# CH32X035F7.net
KiCad netlist of a schematic drawn in Altium Designer
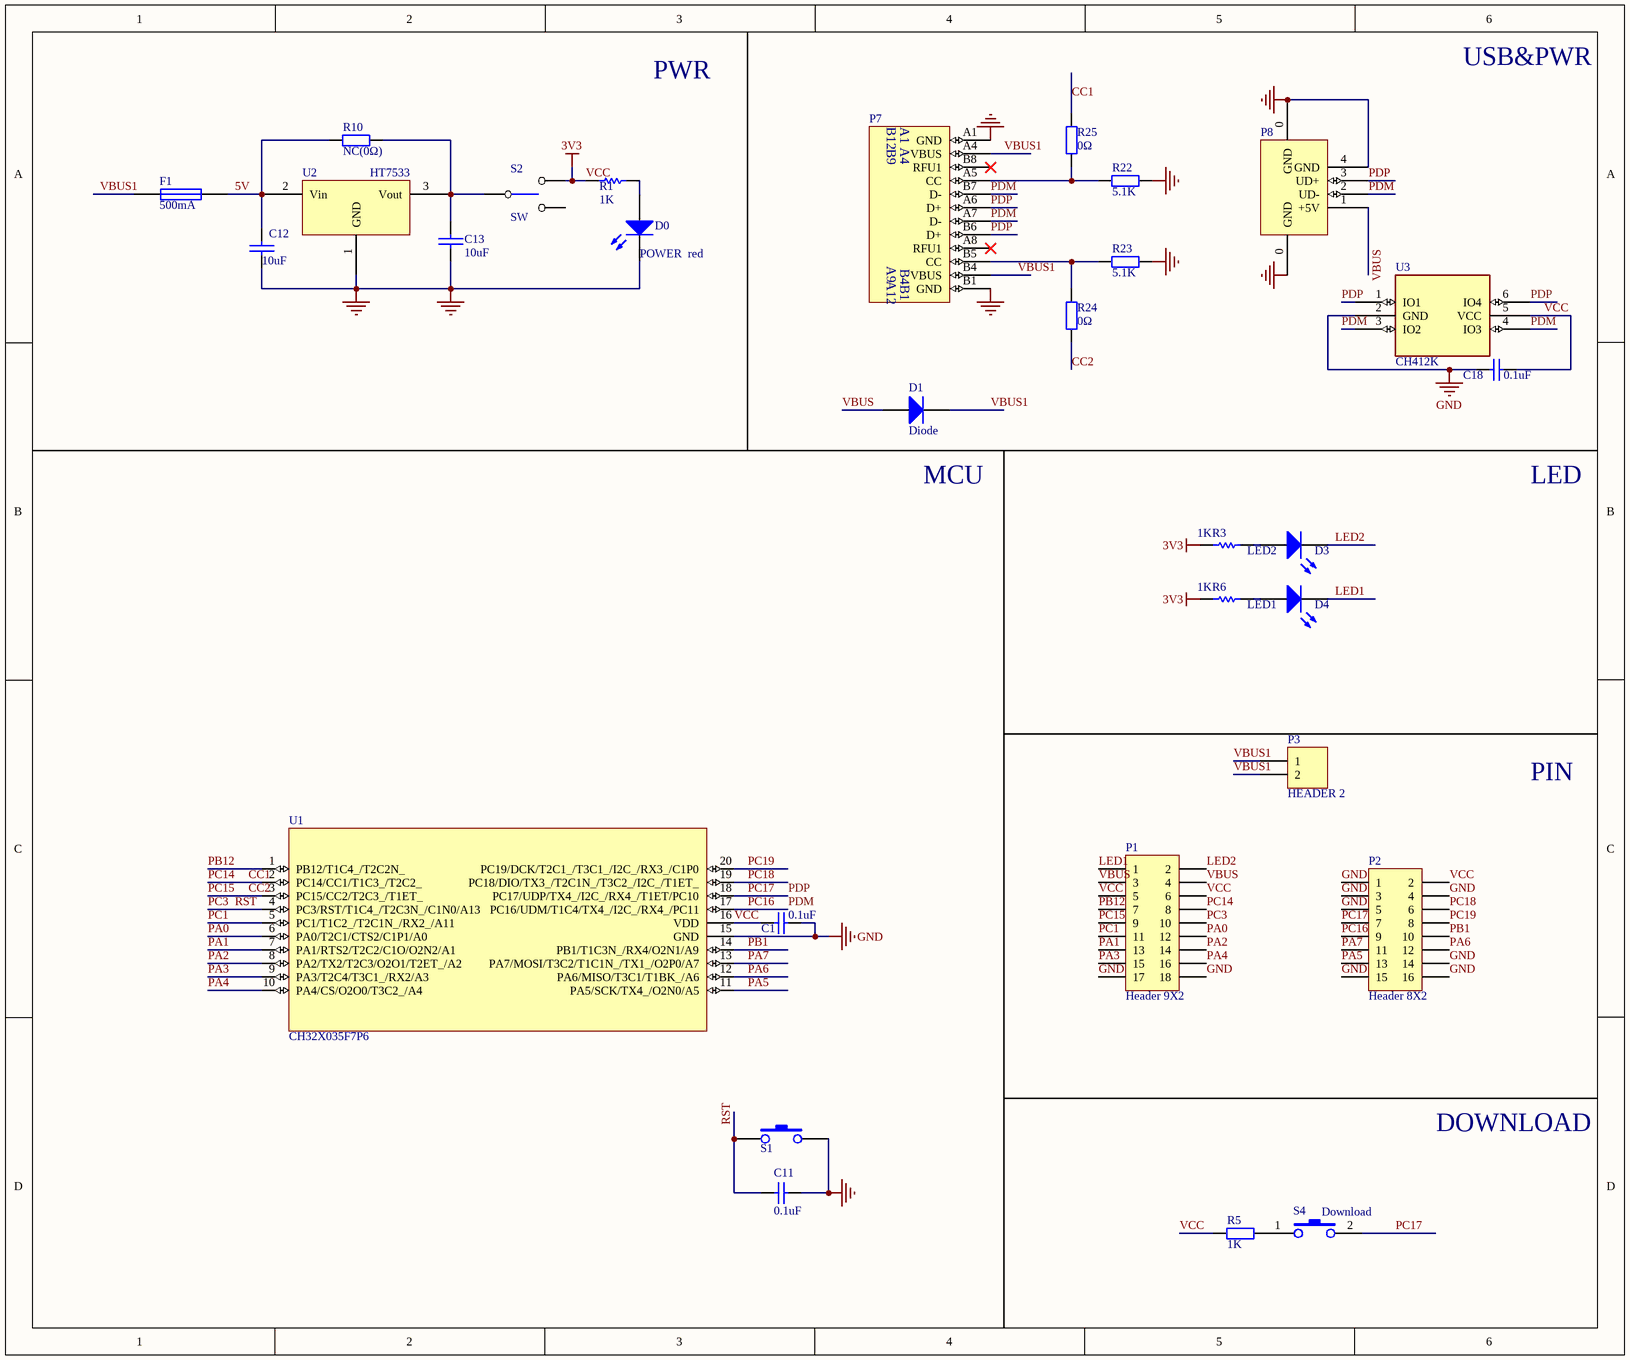
[diagram p0: CH32X035F7.SchDoc]

(export (version "E")
  (design (tool "Eeschema 10.0.6"))
  (components
    (comp (ref "C1")
      (value "0.1uF")
      (footprint "0603_C")
      (description "Capacitor")
      (libsource (lib "Miscellaneous Devices") (part "Cap"))
    )
    (comp (ref "C11")
      (value "0.1uF")
      (footprint "0603_C")
      (description "Capacitor")
      (fields (field (name "PUBLISHER") "Altium Limited"))
      (libsource (lib "*") (part "Cap"))
    )
    (comp (ref "C12")
      (value "10uF")
      (footprint "0603_C")
      (description "Capacitor")
      (libsource (lib "*") (part "CAP"))
    )
    (comp (ref "C13")
      (value "10uF")
      (footprint "0603_C")
      (description "Capacitor")
      (libsource (lib "*") (part "CAP"))
    )
    (comp (ref "C18")
      (value "0.1uF")
      (footprint "0603_C")
      (description "Capacitor")
      (libsource (lib "Miscellaneous Devices") (part "Cap"))
    )
    (comp (ref "D0")
      (value "POWER  red")
      (footprint "0603+")
      (description "Typical INFRARED GaAs LED")
      (fields (field (name "PUBLISHER") "Altium Limited"))
      (libsource (lib "*") (part "LED0"))
    )
    (comp (ref "D1")
      (value "Diode")
      (footprint "SOD-123")
      (description "Default Diode")
      (fields (field (name "PUBLISHER") "Altium Limited"))
      (libsource (lib "Miscellaneous Devices") (part "Diode"))
    )
    (comp (ref "D3")
      (value "LED2")
      (footprint "0603+")
      (description "Typical INFRARED GaAs LED")
      (fields (field (name "PUBLISHER") "Altium Limited"))
      (libsource (lib "*") (part "LED0"))
    )
    (comp (ref "D4")
      (value "LED1")
      (footprint "0603+")
      (description "Typical INFRARED GaAs LED")
      (fields (field (name "PUBLISHER") "Altium Limited"))
      (libsource (lib "*") (part "LED0"))
    )
    (comp (ref "F1")
      (value "500mA")
      (footprint "0603")
      (description "Fuse")
      (libsource (lib "*") (part "FUSE1"))
    )
    (comp (ref "P1")
      (value "Header 9X2")
      (footprint "IDC18-2.54mm")
      (description "Header, 9-Pin, Dual row")
      (fields (field (name "PUBLISHER") "Altium Limited"))
      (libsource (lib "Miscellaneous Connectors") (part "Header 9X2"))
    )
    (comp (ref "P2")
      (value "Header 8X2")
      (footprint "IDC16-2.54mm")
      (description "Header, 8-Pin, Dual row")
      (fields (field (name "PUBLISHER") "Altium Limited"))
      (libsource (lib "Miscellaneous Connectors") (part "Header 8X2"))
    )
    (comp (ref "P3")
      (value "HEADER 2")
      (footprint "SIP2-2.54mm")
      (description "Header, 2-Pin")
      (libsource (lib "wch_sch_others") (part "HEADER 2"))
    )
    (comp (ref "P7")
      (value "TYPE-C")
      (footprint "TYPE-C-Receptacle-2.0")
      (libsource (lib "*") (part "TYPE-C1"))
    )
    (comp (ref "P8")
      (value "USB_A")
      (footprint "USBAF")
      (description "USB Port")
      (libsource (lib "*") (part "USB"))
    )
    (comp (ref "R1")
      (value "1K")
      (footprint "0603")
      (description "Semiconductor Resistor")
      (libsource (lib "*") (part "Res Semi"))
    )
    (comp (ref "R3")
      (value "1K")
      (footprint "0603")
      (description "Semiconductor Resistor")
      (libsource (lib "*") (part "Res Semi"))
    )
    (comp (ref "R5")
      (value "1K")
      (footprint "0603")
      (description "Resistor")
      (libsource (lib "Miscellaneous Devices") (part "Res2"))
    )
    (comp (ref "R6")
      (value "1K")
      (footprint "0603")
      (description "Semiconductor Resistor")
      (libsource (lib "*") (part "Res Semi"))
    )
    (comp (ref "R10")
      (value "NC(0Ω)")
      (footprint "0603")
      (description "Resistor")
      (libsource (lib "*") (part "Res2"))
    )
    (comp (ref "R22")
      (value "5.1K")
      (footprint "0603")
      (description "Resistor")
      (libsource (lib "Miscellaneous Devices") (part "Res2"))
    )
    (comp (ref "R23")
      (value "5.1K")
      (footprint "0603")
      (description "Resistor")
      (libsource (lib "Miscellaneous Devices") (part "Res2"))
    )
    (comp (ref "R24")
      (value "0Ω")
      (footprint "0603")
      (description "Resistor")
      (libsource (lib "") (part "Res2_1"))
    )
    (comp (ref "R25")
      (value "0Ω")
      (footprint "0603")
      (description "Resistor")
      (libsource (lib "") (part "Res2_1"))
    )
    (comp (ref "S1") (value "KEY") (footprint "贴片按键") (libsource (lib "*") (part "KEY")))
    (comp (ref "S2") (value "SW") (footprint "SW1") (libsource (lib "*") (part "SW")))
    (comp (ref "S4")
      (value "Download")
      (footprint "SMD_6.1x3.65x2.5mm-KEY")
      (libsource (lib "wch_sch_others") (part "KEY1"))
    )
    (comp (ref "U1")
      (value "CH32X035F7P6")
      (footprint "TSSOP20")
      (description "RISC-V MCU with USB/PD/ADC/SPI/I2C/UART/OA/CMP")
      (libsource (lib "DHXXXSCH") (part "CH32X035F7P6"))
    )
    (comp (ref "U2")
      (value "HT7533")
      (footprint "SOT-89")
      (libsource (lib "wch_sch_others") (part "1117-3.3V"))
    )
    (comp (ref "U3")
      (value "CH412K")
      (footprint "SOT-363")
      (description "Qaud ESD protect, high speed")
      (libsource (lib "CHXXX") (part "CH412K"))
    )
  )
  (nets
    (net (code "1") (name "/5V") (class "Default")
      (node (ref "C12") (pin "1") (pinfunction "1_1") (pintype "passive"))
      (node (ref "F1") (pin "2") (pinfunction "2_2") (pintype "passive"))
      (node (ref "R10") (pin "2") (pinfunction "2_2") (pintype "passive"))
      (node (ref "U2") (pin "2") (pinfunction "Vin_2") (pintype "passive"))
    )
    (net (code "3") (name "/CC1") (class "Default")
      (node (ref "P1") (pin "8") (pinfunction "8_8") (pintype "passive"))
      (node (ref "R25") (pin "2") (pinfunction "2_2") (pintype "passive"))
      (node (ref "U1") (pin "2") (pinfunction "PC14/CC1/T1C3_/T2C2__2") (pintype "bidirectional"))
    )
    (net (code "4") (name "/CC2") (class "Default")
      (node (ref "P1") (pin "9") (pinfunction "9_9") (pintype "passive"))
      (node (ref "R24") (pin "1") (pinfunction "1_1") (pintype "passive"))
      (node (ref "U1") (pin "3") (pinfunction "PC15/CC2/T2C3_/T1ET__3") (pintype "bidirectional"))
    )
    (net (code "5") (name "/LED1") (class "Default")
      (node (ref "D4") (pin "2") (pinfunction "K_2") (pintype "passive"))
      (node (ref "P1") (pin "1") (pinfunction "1_1") (pintype "passive"))
    )
    (net (code "6") (name "/LED2") (class "Default")
      (node (ref "D3") (pin "2") (pinfunction "K_2") (pintype "passive"))
      (node (ref "P1") (pin "2") (pinfunction "2_2") (pintype "passive"))
    )
    (net (code "7") (name "/PA0") (class "Default")
      (node (ref "P1") (pin "12") (pinfunction "12_12") (pintype "passive"))
      (node (ref "U1") (pin "6") (pinfunction "PA0/T2C1/CTS2/C1P1/A0_6") (pintype "bidirectional"))
    )
    (net (code "8") (name "/PA1") (class "Default")
      (node (ref "P1") (pin "13") (pinfunction "13_13") (pintype "passive"))
      (node (ref "U1") (pin "7") (pinfunction "PA1/RTS2/T2C2/C1O/O2N2/A1_7") (pintype "bidirectional"))
    )
    (net (code "9") (name "/PA2") (class "Default")
      (node (ref "P1") (pin "14") (pinfunction "14_14") (pintype "passive"))
      (node (ref "U1") (pin "8") (pinfunction "PA2/TX2/T2C3/O2O1/T2ET_/A2_8") (pintype "bidirectional"))
    )
    (net (code "10") (name "/PA3") (class "Default")
      (node (ref "P1") (pin "15") (pinfunction "15_15") (pintype "passive"))
      (node (ref "U1") (pin "9") (pinfunction "PA3/T2C4/T3C1_/RX2/A3_9") (pintype "bidirectional"))
    )
    (net (code "11") (name "/PA4") (class "Default")
      (node (ref "P1") (pin "16") (pinfunction "16_16") (pintype "passive"))
      (node (ref "U1") (pin "10") (pinfunction "PA4/CS/O2O0/T3C2_/A4_10") (pintype "bidirectional"))
    )
    (net (code "12") (name "/PA5") (class "Default")
      (node (ref "P2") (pin "13") (pinfunction "13_13") (pintype "passive"))
      (node (ref "U1") (pin "11") (pinfunction "PA5/SCK/TX4_/O2N0/A5_11") (pintype "bidirectional"))
    )
    (net (code "13") (name "/PA6") (class "Default")
      (node (ref "P2") (pin "12") (pinfunction "12_12") (pintype "passive"))
      (node (ref "U1") (pin "12") (pinfunction "PA6/MISO/T3C1/T1BK_/A6_12") (pintype "bidirectional"))
    )
    (net (code "14") (name "/PA7") (class "Default")
      (node (ref "P2") (pin "11") (pinfunction "11_11") (pintype "passive"))
      (node (ref "U1") (pin "13") (pinfunction "PA7/MOSI/T3C2/T1C1N_/TX1_/O2P0/A7_13") (pintype "bidirectional"))
    )
    (net (code "15") (name "/PB1") (class "Default")
      (node (ref "P2") (pin "10") (pinfunction "10_10") (pintype "passive"))
      (node (ref "U1") (pin "14") (pinfunction "PB1/T1C3N_/RX4/O2N1/A9_14") (pintype "bidirectional"))
    )
    (net (code "16") (name "/PB12") (class "Default")
      (node (ref "P1") (pin "7") (pinfunction "7_7") (pintype "passive"))
      (node (ref "U1") (pin "1") (pinfunction "PB12/T1C4_/T2C2N__1") (pintype "bidirectional"))
    )
    (net (code "17") (name "/PC1") (class "Default")
      (node (ref "P1") (pin "11") (pinfunction "11_11") (pintype "passive"))
      (node (ref "U1") (pin "5") (pinfunction "PC1/T1C2_/T2C1N_/RX2_/A11_5") (pintype "bidirectional"))
    )
    (net (code "18") (name "/PC3") (class "Default")
      (node (ref "C11") (pin "2") (pinfunction "2_2") (pintype "passive"))
      (node (ref "P1") (pin "10") (pinfunction "10_10") (pintype "passive"))
      (node (ref "S1") (pin "1") (pinfunction "1_1") (pintype "passive"))
      (node (ref "U1") (pin "4") (pinfunction "PC3/RST/T1C4_/T2C3N_/C1N0/A13_4") (pintype "bidirectional"))
    )
    (net (code "19") (name "/PC16") (class "Default")
      (node (ref "P2") (pin "9") (pinfunction "9_9") (pintype "passive"))
      (node (ref "P7") (pin "A7") (pinfunction "D-_A7") (pintype "bidirectional"))
      (node (ref "P7") (pin "B7") (pinfunction "D-_B7") (pintype "bidirectional"))
      (node (ref "P8") (pin "2") (pinfunction "UD-_2") (pintype "bidirectional"))
      (node (ref "U1") (pin "17") (pinfunction "PC16/UDM/T1C4/TX4_/I2C_/RX4_/PC11_17") (pintype "bidirectional"))
      (node (ref "U3") (pin "3") (pinfunction "IO2_3") (pintype "bidirectional"))
      (node (ref "U3") (pin "4") (pinfunction "IO3_4") (pintype "bidirectional"))
    )
    (net (code "20") (name "/PC17") (class "Default")
      (node (ref "P2") (pin "7") (pinfunction "7_7") (pintype "passive"))
      (node (ref "P7") (pin "A6") (pinfunction "D+_A6") (pintype "bidirectional"))
      (node (ref "P7") (pin "B6") (pinfunction "D+_B6") (pintype "bidirectional"))
      (node (ref "P8") (pin "3") (pinfunction "UD+_3") (pintype "bidirectional"))
      (node (ref "S4") (pin "2") (pinfunction "2_2") (pintype "passive"))
      (node (ref "U1") (pin "18") (pinfunction "PC17/UDP/TX4_/I2C_/RX4_/T1ET/PC10_18") (pintype "bidirectional"))
      (node (ref "U3") (pin "1") (pinfunction "IO1_1") (pintype "bidirectional"))
      (node (ref "U3") (pin "6") (pinfunction "IO4_6") (pintype "bidirectional"))
    )
    (net (code "21") (name "/PC18") (class "Default")
      (node (ref "P2") (pin "6") (pinfunction "6_6") (pintype "passive"))
      (node (ref "U1") (pin "19") (pinfunction "PC18/DIO/TX3_/T2C1N_/T3C2_/I2C_/T1ET__19") (pintype "bidirectional"))
    )
    (net (code "22") (name "/PC19") (class "Default")
      (node (ref "P2") (pin "8") (pinfunction "8_8") (pintype "passive"))
      (node (ref "U1") (pin "20") (pinfunction "PC19/DCK/T2C1_/T3C1_/I2C_/RX3_/C1P0_20") (pintype "bidirectional"))
    )
    (net (code "23") (name "/VBUS") (class "Default")
      (node (ref "D1") (pin "1") (pinfunction "A_1") (pintype "passive"))
      (node (ref "P1") (pin "3") (pinfunction "3_3") (pintype "passive"))
      (node (ref "P1") (pin "4") (pinfunction "4_4") (pintype "passive"))
      (node (ref "P8") (pin "1") (pinfunction "+5V_1") (pintype "power_in"))
    )
    (net (code "24") (name "/VBUS1") (class "Default")
      (node (ref "D1") (pin "2") (pinfunction "K_2") (pintype "passive"))
      (node (ref "F1") (pin "1") (pinfunction "1_1") (pintype "passive"))
      (node (ref "P3") (pin "1") (pinfunction "1_1") (pintype "passive"))
      (node (ref "P3") (pin "2") (pinfunction "2_2") (pintype "passive"))
      (node (ref "P7") (pin "A4") (pinfunction "VBUS_A4") (pintype "bidirectional"))
      (node (ref "P7") (pin "B4") (pinfunction "VBUS_B4") (pintype "bidirectional"))
    )
    (net (code "25") (name "3V3") (class "Default")
      (node (ref "C1") (pin "2") (pinfunction "2_2") (pintype "passive"))
      (node (ref "C18") (pin "2") (pinfunction "2_2") (pintype "passive"))
      (node (ref "P1") (pin "5") (pinfunction "5_5") (pintype "passive"))
      (node (ref "P1") (pin "6") (pinfunction "6_6") (pintype "passive"))
      (node (ref "P2") (pin "2") (pinfunction "2_2") (pintype "passive"))
      (node (ref "R1") (pin "2") (pinfunction "2_2") (pintype "passive"))
      (node (ref "R3") (pin "1") (pinfunction "1_1") (pintype "passive"))
      (node (ref "R5") (pin "1") (pinfunction "1_1") (pintype "passive"))
      (node (ref "R6") (pin "1") (pinfunction "1_1") (pintype "passive"))
      (node (ref "S2") (pin "3") (pinfunction "3_3") (pintype "passive"))
      (node (ref "U1") (pin "16") (pinfunction "VDD_16") (pintype "power_in"))
      (node (ref "U3") (pin "5") (pinfunction "VCC_5") (pintype "power_in"))
    )
    (net (code "26") (name "GND") (class "Default")
      (node (ref "C1") (pin "1") (pinfunction "1_1") (pintype "passive"))
      (node (ref "C11") (pin "1") (pinfunction "1_1") (pintype "passive"))
      (node (ref "C12") (pin "2") (pinfunction "2_2") (pintype "passive"))
      (node (ref "C13") (pin "2") (pinfunction "2_2") (pintype "passive"))
      (node (ref "C18") (pin "1") (pinfunction "1_1") (pintype "passive"))
      (node (ref "D0") (pin "2") (pinfunction "K_2") (pintype "passive"))
      (node (ref "P1") (pin "17") (pinfunction "17_17") (pintype "passive"))
      (node (ref "P1") (pin "18") (pinfunction "18_18") (pintype "passive"))
      (node (ref "P2") (pin "1") (pinfunction "1_1") (pintype "passive"))
      (node (ref "P2") (pin "14") (pinfunction "14_14") (pintype "passive"))
      (node (ref "P2") (pin "15") (pinfunction "15_15") (pintype "passive"))
      (node (ref "P2") (pin "16") (pinfunction "16_16") (pintype "passive"))
      (node (ref "P2") (pin "3") (pinfunction "3_3") (pintype "passive"))
      (node (ref "P2") (pin "4") (pinfunction "4_4") (pintype "passive"))
      (node (ref "P2") (pin "5") (pinfunction "5_5") (pintype "passive"))
      (node (ref "P7") (pin "A1") (pinfunction "GND_A1") (pintype "bidirectional"))
      (node (ref "P7") (pin "B1") (pinfunction "GND_B1") (pintype "bidirectional"))
      (node (ref "P8") (pin "0") (pinfunction "GND_0") (pintype "power_in"))
      (node (ref "P8") (pin "4") (pinfunction "GND_4") (pintype "power_in"))
      (node (ref "R22") (pin "2") (pinfunction "2_2") (pintype "passive"))
      (node (ref "R23") (pin "2") (pinfunction "2_2") (pintype "passive"))
      (node (ref "S1") (pin "2") (pinfunction "2_2") (pintype "passive"))
      (node (ref "U1") (pin "15") (pinfunction "GND_15") (pintype "power_in"))
      (node (ref "U2") (pin "1") (pinfunction "GND_1") (pintype "passive"))
      (node (ref "U3") (pin "2") (pinfunction "GND_2") (pintype "power_in"))
    )
    (net (code "27") (name "Net-(D0-A)") (class "Default")
      (node (ref "D0") (pin "1") (pinfunction "A_1") (pintype "passive"))
      (node (ref "R1") (pin "1") (pinfunction "1_1") (pintype "passive"))
    )
    (net (code "28") (name "Net-(D3-A)") (class "Default")
      (node (ref "D3") (pin "1") (pinfunction "A_1") (pintype "passive"))
      (node (ref "R3") (pin "2") (pinfunction "2_2") (pintype "passive"))
    )
    (net (code "29") (name "Net-(D4-A)") (class "Default")
      (node (ref "D4") (pin "1") (pinfunction "A_1") (pintype "passive"))
      (node (ref "R6") (pin "2") (pinfunction "2_2") (pintype "passive"))
    )
    (net (code "30") (name "Net-(P7-CC-PadA5)") (class "Default")
      (node (ref "P7") (pin "A5") (pinfunction "CC_A5") (pintype "bidirectional"))
      (node (ref "R22") (pin "1") (pinfunction "1_1") (pintype "passive"))
      (node (ref "R25") (pin "1") (pinfunction "1_1") (pintype "passive"))
    )
    (net (code "31") (name "Net-(P7-CC-PadB5)") (class "Default")
      (node (ref "P7") (pin "B5") (pinfunction "CC_B5") (pintype "bidirectional"))
      (node (ref "R23") (pin "1") (pinfunction "1_1") (pintype "passive"))
      (node (ref "R24") (pin "2") (pinfunction "2_2") (pintype "passive"))
    )
    (net (code "32") (name "Net-(R5-Pad2)") (class "Default")
      (node (ref "R5") (pin "2") (pinfunction "2_2") (pintype "passive"))
      (node (ref "S4") (pin "1") (pinfunction "1_1") (pintype "passive"))
    )
    (net (code "33") (name "Net-(U2-Vout)") (class "Default")
      (node (ref "C13") (pin "1") (pinfunction "1_1") (pintype "passive"))
      (node (ref "R10") (pin "1") (pinfunction "1_1") (pintype "passive"))
      (node (ref "S2") (pin "1") (pinfunction "1_1") (pintype "passive"))
      (node (ref "U2") (pin "3") (pinfunction "Vout_3") (pintype "passive"))
    )
    (net (code "34") (name "unconnected-(P7-RFU1-PadA8)") (class "Default")
      (node (ref "P7") (pin "A8") (pinfunction "RFU1_A8") (pintype "bidirectional+no_connect"))
    )
    (net (code "35") (name "unconnected-(P7-RFU1-PadB8)") (class "Default")
      (node (ref "P7") (pin "B8") (pinfunction "RFU1_B8") (pintype "bidirectional+no_connect"))
    )
    (net (code "36") (name "unconnected-(S2-Pad2)") (class "Default")
      (node (ref "S2") (pin "2") (pinfunction "2_2") (pintype "passive"))
    )
  )
)
